# ds2_redraw.net
KiCad netlist of a schematic drawn in EAGLE
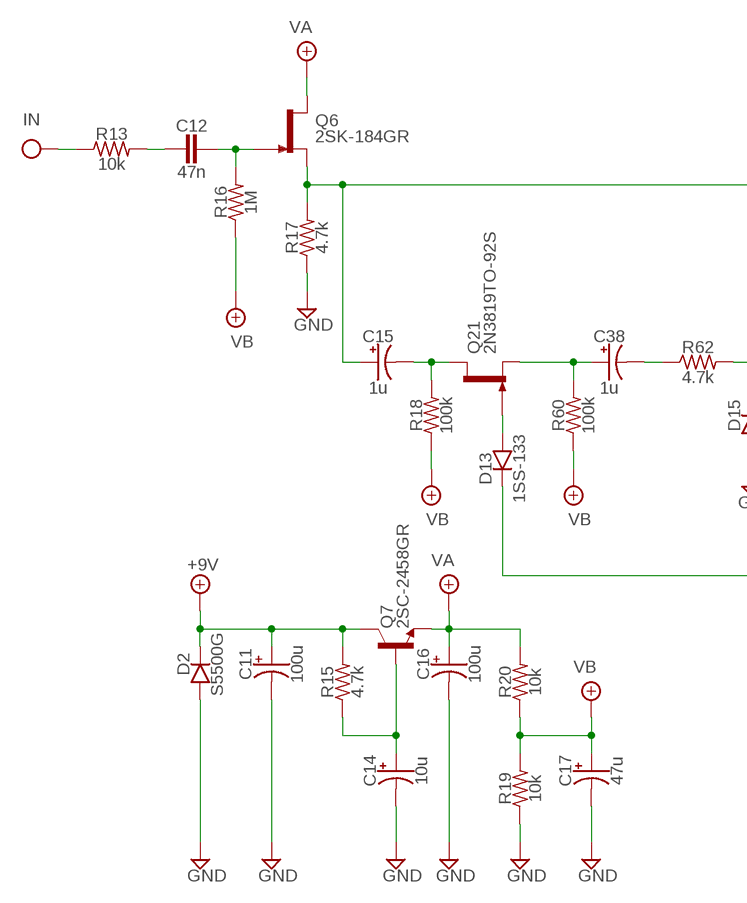
[diagram p0: schematic, sheet 1, part 1 of 2]
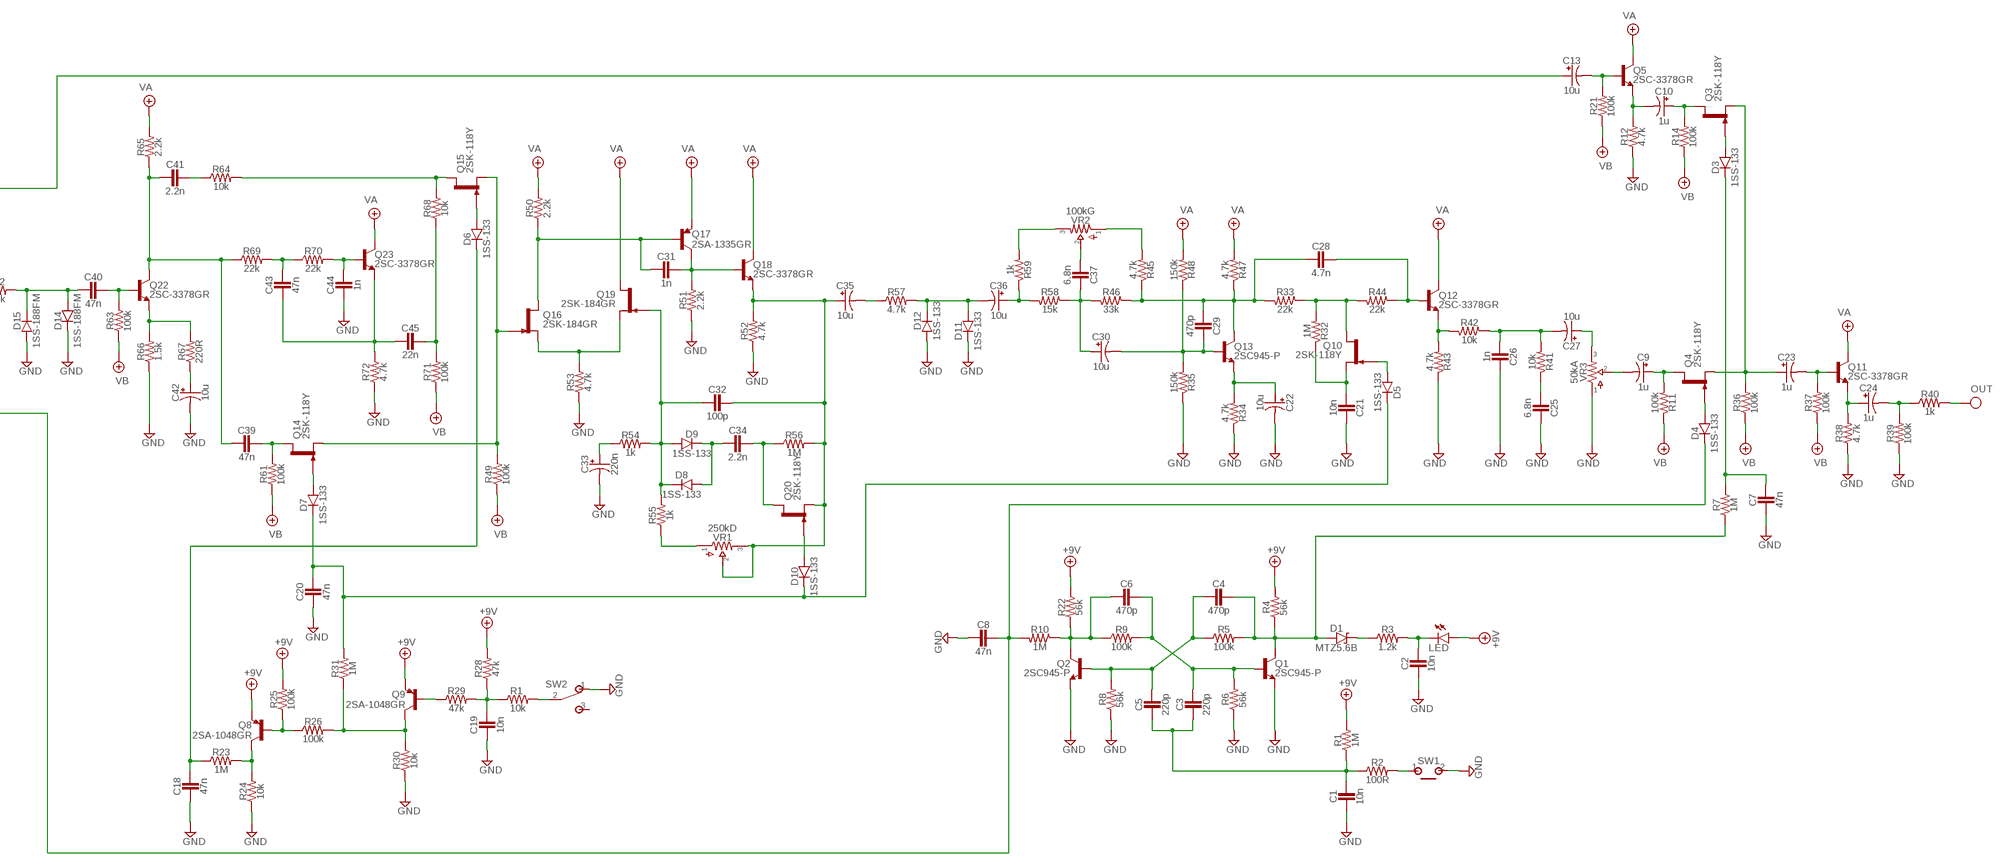
[diagram p1: schematic, sheet 1, part 2 of 2]

(export (version "E")
  (design (tool "Eeschema 10.0.6"))
  (components
    (comp (ref "C1")
      (value "10n")
      (footprint "eagle-import:BOX_SMALL")
      (libsource (lib "eagle-import") (part "CER/FILMBOX.1"))
    )
    (comp (ref "C2")
      (value "10n")
      (footprint "eagle-import:BOX_SMALL")
      (libsource (lib "eagle-import") (part "CER/FILMBOX.1"))
    )
    (comp (ref "C3")
      (value "220p")
      (footprint "eagle-import:BOX_SMALL")
      (libsource (lib "eagle-import") (part "CER/FILMBOX.1"))
    )
    (comp (ref "C4")
      (value "470p")
      (footprint "eagle-import:BOX_SMALL")
      (libsource (lib "eagle-import") (part "CER/FILMBOX.1"))
    )
    (comp (ref "C5")
      (value "220p")
      (footprint "eagle-import:BOX_SMALL")
      (libsource (lib "eagle-import") (part "CER/FILMBOX.1"))
    )
    (comp (ref "C6")
      (value "470p")
      (footprint "eagle-import:BOX_SMALL")
      (libsource (lib "eagle-import") (part "CER/FILMBOX.1"))
    )
    (comp (ref "C7")
      (value "47n")
      (footprint "eagle-import:BOX_SMALL")
      (libsource (lib "eagle-import") (part "CER/FILMBOX.1"))
    )
    (comp (ref "C8")
      (value "47n")
      (footprint "eagle-import:BOX_SMALL")
      (libsource (lib "eagle-import") (part "CER/FILMBOX.1"))
    )
    (comp (ref "C9")
      (value "1u")
      (footprint "eagle-import:040_020")
      (libsource (lib "eagle-import") (part "0400"))
    )
    (comp (ref "C10")
      (value "1u")
      (footprint "eagle-import:040_020")
      (libsource (lib "eagle-import") (part "0400"))
    )
    (comp (ref "C11")
      (value "100u")
      (footprint "eagle-import:040_020")
      (libsource (lib "eagle-import") (part "0400"))
    )
    (comp (ref "C12")
      (value "47n")
      (footprint "eagle-import:BOX_SMALL")
      (libsource (lib "eagle-import") (part "CER/FILMBOX.1"))
    )
    (comp (ref "C13")
      (value "10u")
      (footprint "eagle-import:040_020")
      (libsource (lib "eagle-import") (part "0400"))
    )
    (comp (ref "C14")
      (value "10u")
      (footprint "eagle-import:040_020")
      (libsource (lib "eagle-import") (part "0400"))
    )
    (comp (ref "C15")
      (value "1u")
      (footprint "eagle-import:040_020")
      (libsource (lib "eagle-import") (part "0400"))
    )
    (comp (ref "C16")
      (value "100u")
      (footprint "eagle-import:040_020")
      (libsource (lib "eagle-import") (part "0400"))
    )
    (comp (ref "C17")
      (value "47u")
      (footprint "eagle-import:040_020")
      (libsource (lib "eagle-import") (part "0400"))
    )
    (comp (ref "C18")
      (value "47n")
      (footprint "eagle-import:BOX_SMALL")
      (libsource (lib "eagle-import") (part "CER/FILMBOX.1"))
    )
    (comp (ref "C19")
      (value "10n")
      (footprint "eagle-import:BOX_SMALL")
      (libsource (lib "eagle-import") (part "CER/FILMBOX.1"))
    )
    (comp (ref "C20")
      (value "47n")
      (footprint "eagle-import:BOX_SMALL")
      (libsource (lib "eagle-import") (part "CER/FILMBOX.1"))
    )
    (comp (ref "C21")
      (value "10n")
      (footprint "eagle-import:BOX_SMALL")
      (libsource (lib "eagle-import") (part "CER/FILMBOX.1"))
    )
    (comp (ref "C22")
      (value "10u")
      (footprint "eagle-import:040_020")
      (libsource (lib "eagle-import") (part "0400"))
    )
    (comp (ref "C23")
      (value "1u")
      (footprint "eagle-import:040_020")
      (libsource (lib "eagle-import") (part "0400"))
    )
    (comp (ref "C24")
      (value "1u")
      (footprint "eagle-import:040_020")
      (libsource (lib "eagle-import") (part "0400"))
    )
    (comp (ref "C25")
      (value "6.8n")
      (footprint "eagle-import:BOX_SMALL")
      (libsource (lib "eagle-import") (part "CER/FILMBOX.1"))
    )
    (comp (ref "C26")
      (value "1n")
      (footprint "eagle-import:BOX_SMALL")
      (libsource (lib "eagle-import") (part "CER/FILMBOX.1"))
    )
    (comp (ref "C27")
      (value "10u")
      (footprint "eagle-import:040_020")
      (libsource (lib "eagle-import") (part "0400"))
    )
    (comp (ref "C28")
      (value "4.7n")
      (footprint "eagle-import:BOX_SMALL")
      (libsource (lib "eagle-import") (part "CER/FILMBOX.1"))
    )
    (comp (ref "C29")
      (value "470p")
      (footprint "eagle-import:BOX_SMALL")
      (libsource (lib "eagle-import") (part "CER/FILMBOX.1"))
    )
    (comp (ref "C30")
      (value "10u")
      (footprint "eagle-import:040_020")
      (libsource (lib "eagle-import") (part "0400"))
    )
    (comp (ref "C31")
      (value "1n")
      (footprint "eagle-import:BOX_SMALL")
      (libsource (lib "eagle-import") (part "CER/FILMBOX.1"))
    )
    (comp (ref "C32")
      (value "100p")
      (footprint "eagle-import:BOX_SMALL")
      (libsource (lib "eagle-import") (part "CER/FILMBOX.1"))
    )
    (comp (ref "C33")
      (value "220n")
      (footprint "eagle-import:040_020")
      (libsource (lib "eagle-import") (part "0400"))
    )
    (comp (ref "C34")
      (value "2.2n")
      (footprint "eagle-import:BOX_SMALL")
      (libsource (lib "eagle-import") (part "CER/FILMBOX.1"))
    )
    (comp (ref "C35")
      (value "10u")
      (footprint "eagle-import:040_020")
      (libsource (lib "eagle-import") (part "0400"))
    )
    (comp (ref "C36")
      (value "10u")
      (footprint "eagle-import:040_020")
      (libsource (lib "eagle-import") (part "0400"))
    )
    (comp (ref "C37")
      (value "6.8n")
      (footprint "eagle-import:BOX_SMALL")
      (libsource (lib "eagle-import") (part "CER/FILMBOX.1"))
    )
    (comp (ref "C38")
      (value "1u")
      (footprint "eagle-import:040_020")
      (libsource (lib "eagle-import") (part "0400"))
    )
    (comp (ref "C39")
      (value "47n")
      (footprint "eagle-import:BOX_SMALL")
      (libsource (lib "eagle-import") (part "CER/FILMBOX.1"))
    )
    (comp (ref "C40")
      (value "47n")
      (footprint "eagle-import:BOX_SMALL")
      (libsource (lib "eagle-import") (part "CER/FILMBOX.1"))
    )
    (comp (ref "C41")
      (value "2.2n")
      (footprint "eagle-import:BOX_SMALL")
      (libsource (lib "eagle-import") (part "CER/FILMBOX.1"))
    )
    (comp (ref "C42")
      (value "10u")
      (footprint "eagle-import:040_020")
      (libsource (lib "eagle-import") (part "0400"))
    )
    (comp (ref "C43")
      (value "47n")
      (footprint "eagle-import:BOX_SMALL")
      (libsource (lib "eagle-import") (part "CER/FILMBOX.1"))
    )
    (comp (ref "C44")
      (value "1n")
      (footprint "eagle-import:BOX_SMALL")
      (libsource (lib "eagle-import") (part "CER/FILMBOX.1"))
    )
    (comp (ref "C45")
      (value "22n")
      (footprint "eagle-import:BOX_SMALL")
      (libsource (lib "eagle-import") (part "CER/FILMBOX.1"))
    )
    (comp (ref "D1")
      (value "MTZ5.6B")
      (footprint "eagle-import:DO41-2")
      (libsource (lib "eagle-import") (part "ZENER.2"))
    )
    (comp (ref "D2")
      (value "S5500G")
      (footprint "eagle-import:DO35-2")
      (libsource (lib "eagle-import") (part "DO35.2"))
    )
    (comp (ref "D3")
      (value "1SS-133")
      (footprint "eagle-import:DO35-2")
      (libsource (lib "eagle-import") (part "DO35.2"))
    )
    (comp (ref "D4")
      (value "1SS-133")
      (footprint "eagle-import:DO35-2")
      (libsource (lib "eagle-import") (part "DO35.2"))
    )
    (comp (ref "D5")
      (value "1SS-133")
      (footprint "eagle-import:DO35-2")
      (libsource (lib "eagle-import") (part "DO35.2"))
    )
    (comp (ref "D6")
      (value "1SS-133")
      (footprint "eagle-import:DO35-2")
      (libsource (lib "eagle-import") (part "DO35.2"))
    )
    (comp (ref "D7")
      (value "1SS-133")
      (footprint "eagle-import:DO35-2")
      (libsource (lib "eagle-import") (part "DO35.2"))
    )
    (comp (ref "D8")
      (value "1SS-133")
      (footprint "eagle-import:DO35-2")
      (libsource (lib "eagle-import") (part "DO35.2"))
    )
    (comp (ref "D9")
      (value "1SS-133")
      (footprint "eagle-import:DO35-2")
      (libsource (lib "eagle-import") (part "DO35.2"))
    )
    (comp (ref "D10")
      (value "1SS-133")
      (footprint "eagle-import:DO35-2")
      (libsource (lib "eagle-import") (part "DO35.2"))
    )
    (comp (ref "D11")
      (value "1SS-133")
      (footprint "eagle-import:DO35-2")
      (libsource (lib "eagle-import") (part "DO35.2"))
    )
    (comp (ref "D12")
      (value "1SS-133")
      (footprint "eagle-import:DO35-2")
      (libsource (lib "eagle-import") (part "DO35.2"))
    )
    (comp (ref "D13")
      (value "1SS-133")
      (footprint "eagle-import:DO35-2")
      (libsource (lib "eagle-import") (part "DO35.2"))
    )
    (comp (ref "D14")
      (value "1SS-188FM")
      (footprint "eagle-import:DO35-2")
      (libsource (lib "eagle-import") (part "DO35.2"))
    )
    (comp (ref "D15")
      (value "1SS-188FM")
      (footprint "eagle-import:DO35-2")
      (libsource (lib "eagle-import") (part "DO35.2"))
    )
    (comp (ref "LED")
      (value "LED")
      (footprint "eagle-import:3MM_D")
      (libsource (lib "eagle-import") (part "LED"))
    )
    (comp (ref "Q1")
      (value "2SC945-P")
      (footprint "eagle-import:TO92-")
      (libsource (lib "eagle-import") (part "2SC828A"))
    )
    (comp (ref "Q2")
      (value "2SC945-P")
      (footprint "eagle-import:TO92-")
      (libsource (lib "eagle-import") (part "2SC828A"))
    )
    (comp (ref "Q3")
      (value "2SK-118Y")
      (footprint "eagle-import:TO92-")
      (libsource (lib "eagle-import") (part "2N3819TO-92S"))
    )
    (comp (ref "Q4")
      (value "2SK-118Y")
      (footprint "eagle-import:TO92-")
      (libsource (lib "eagle-import") (part "2N3819TO-92S"))
    )
    (comp (ref "Q5")
      (value "2SC-3378GR")
      (footprint "eagle-import:TO92-")
      (libsource (lib "eagle-import") (part "2SC828A"))
    )
    (comp (ref "Q6")
      (value "2SK-184GR")
      (footprint "eagle-import:TO92-")
      (libsource (lib "eagle-import") (part "2N3819TO-92S"))
    )
    (comp (ref "Q7")
      (value "2SC-2458GR")
      (footprint "eagle-import:TO92-")
      (libsource (lib "eagle-import") (part "2SC828A"))
    )
    (comp (ref "Q8")
      (value "2SA-1048GR")
      (footprint "eagle-import:TO92-")
      (libsource (lib "eagle-import") (part "2N3906-"))
    )
    (comp (ref "Q9")
      (value "2SA-1048GR")
      (footprint "eagle-import:TO92-")
      (libsource (lib "eagle-import") (part "2N3906-"))
    )
    (comp (ref "Q10")
      (value "2SK-118Y")
      (footprint "eagle-import:TO92-")
      (libsource (lib "eagle-import") (part "2N3819TO-92S"))
    )
    (comp (ref "Q11")
      (value "2SC-3378GR")
      (footprint "eagle-import:TO92-")
      (libsource (lib "eagle-import") (part "2SC828A"))
    )
    (comp (ref "Q12")
      (value "2SC-3378GR")
      (footprint "eagle-import:TO92-")
      (libsource (lib "eagle-import") (part "2SC828A"))
    )
    (comp (ref "Q13")
      (value "2SC945-P")
      (footprint "eagle-import:TO92-")
      (libsource (lib "eagle-import") (part "2SC828A"))
    )
    (comp (ref "Q14")
      (value "2SK-118Y")
      (footprint "eagle-import:TO92-")
      (libsource (lib "eagle-import") (part "2N3819TO-92S"))
    )
    (comp (ref "Q15")
      (value "2SK-118Y")
      (footprint "eagle-import:TO92-")
      (libsource (lib "eagle-import") (part "2N3819TO-92S"))
    )
    (comp (ref "Q16")
      (value "2SK-184GR")
      (footprint "eagle-import:TO92-")
      (libsource (lib "eagle-import") (part "2N3819TO-92S"))
    )
    (comp (ref "Q17")
      (value "2SA-1335GR")
      (footprint "eagle-import:TO92-")
      (libsource (lib "eagle-import") (part "2N3906-"))
    )
    (comp (ref "Q18")
      (value "2SC-3378GR")
      (footprint "eagle-import:TO92-")
      (libsource (lib "eagle-import") (part "2SC828A"))
    )
    (comp (ref "Q19")
      (value "2SK-184GR")
      (footprint "eagle-import:TO92-")
      (libsource (lib "eagle-import") (part "2N3819TO-92S"))
    )
    (comp (ref "Q20")
      (value "2SK-118Y")
      (footprint "eagle-import:TO92-")
      (libsource (lib "eagle-import") (part "2N3819TO-92S"))
    )
    (comp (ref "Q21")
      (value "2N3819TO-92S")
      (footprint "eagle-import:TO92-")
      (libsource (lib "eagle-import") (part "2N3819TO-92S"))
    )
    (comp (ref "Q22")
      (value "2SC-3378GR")
      (footprint "eagle-import:TO92-")
      (libsource (lib "eagle-import") (part "2SC828A"))
    )
    (comp (ref "Q23")
      (value "2SC-3378GR")
      (footprint "eagle-import:TO92-")
      (libsource (lib "eagle-import") (part "2SC828A"))
    )
    (comp (ref "R1")
      (value "1M")
      (footprint "eagle-import:R0207_3")
      (libsource (lib "eagle-import") (part "R_.3B"))
    )
    (comp (ref "R1 ")
      (value "10k")
      (footprint "eagle-import:R0207_3")
      (libsource (lib "eagle-import") (part "R_.3B"))
    )
    (comp (ref "R2")
      (value "100R")
      (footprint "eagle-import:R0207_3")
      (libsource (lib "eagle-import") (part "R_.3B"))
    )
    (comp (ref "R3")
      (value "1.2k")
      (footprint "eagle-import:R0207_3")
      (libsource (lib "eagle-import") (part "R_.3B"))
    )
    (comp (ref "R4")
      (value "56k")
      (footprint "eagle-import:R0207_3")
      (libsource (lib "eagle-import") (part "R_.3B"))
    )
    (comp (ref "R5")
      (value "100k")
      (footprint "eagle-import:R0207_3")
      (libsource (lib "eagle-import") (part "R_.3B"))
    )
    (comp (ref "R6")
      (value "56k")
      (footprint "eagle-import:R0207_3")
      (libsource (lib "eagle-import") (part "R_.3B"))
    )
    (comp (ref "R7")
      (value "1M")
      (footprint "eagle-import:R0207_3")
      (libsource (lib "eagle-import") (part "R_.3B"))
    )
    (comp (ref "R8")
      (value "56k")
      (footprint "eagle-import:R0207_3")
      (libsource (lib "eagle-import") (part "R_.3B"))
    )
    (comp (ref "R9")
      (value "100k")
      (footprint "eagle-import:R0207_3")
      (libsource (lib "eagle-import") (part "R_.3B"))
    )
    (comp (ref "R10")
      (value "1M")
      (footprint "eagle-import:R0207_3")
      (libsource (lib "eagle-import") (part "R_.3B"))
    )
    (comp (ref "R11")
      (value "100k")
      (footprint "eagle-import:R0207_3")
      (libsource (lib "eagle-import") (part "R_.3B"))
    )
    (comp (ref "R12")
      (value "4.7k")
      (footprint "eagle-import:R0207_3")
      (libsource (lib "eagle-import") (part "R_.3B"))
    )
    (comp (ref "R13")
      (value "10k")
      (footprint "eagle-import:R0207_3")
      (libsource (lib "eagle-import") (part "R_.3B"))
    )
    (comp (ref "R14")
      (value "100k")
      (footprint "eagle-import:R0207_3")
      (libsource (lib "eagle-import") (part "R_.3B"))
    )
    (comp (ref "R15")
      (value "4.7k")
      (footprint "eagle-import:R0207_3")
      (libsource (lib "eagle-import") (part "R_.3B"))
    )
    (comp (ref "R16")
      (value "1M")
      (footprint "eagle-import:R0207_3")
      (libsource (lib "eagle-import") (part "R_.3B"))
    )
    (comp (ref "R17")
      (value "4.7k")
      (footprint "eagle-import:R0207_3")
      (libsource (lib "eagle-import") (part "R_.3B"))
    )
    (comp (ref "R18")
      (value "100k")
      (footprint "eagle-import:R0207_3")
      (libsource (lib "eagle-import") (part "R_.3B"))
    )
    (comp (ref "R19")
      (value "10k")
      (footprint "eagle-import:R0207_3")
      (libsource (lib "eagle-import") (part "R_.3B"))
    )
    (comp (ref "R20")
      (value "10k")
      (footprint "eagle-import:R0207_3")
      (libsource (lib "eagle-import") (part "R_.3B"))
    )
    (comp (ref "R21")
      (value "100k")
      (footprint "eagle-import:R0207_3")
      (libsource (lib "eagle-import") (part "R_.3B"))
    )
    (comp (ref "R22")
      (value "56k")
      (footprint "eagle-import:R0207_3")
      (libsource (lib "eagle-import") (part "R_.3B"))
    )
    (comp (ref "R23")
      (value "1M")
      (footprint "eagle-import:R0207_3")
      (libsource (lib "eagle-import") (part "R_.3B"))
    )
    (comp (ref "R24")
      (value "10k")
      (footprint "eagle-import:R0207_3")
      (libsource (lib "eagle-import") (part "R_.3B"))
    )
    (comp (ref "R25")
      (value "100k")
      (footprint "eagle-import:R0207_3")
      (libsource (lib "eagle-import") (part "R_.3B"))
    )
    (comp (ref "R26")
      (value "100k")
      (footprint "eagle-import:R0207_3")
      (libsource (lib "eagle-import") (part "R_.3B"))
    )
    (comp (ref "R28")
      (value "47k")
      (footprint "eagle-import:R0207_3")
      (libsource (lib "eagle-import") (part "R_.3B"))
    )
    (comp (ref "R29")
      (value "47k")
      (footprint "eagle-import:R0207_3")
      (libsource (lib "eagle-import") (part "R_.3B"))
    )
    (comp (ref "R30")
      (value "10k")
      (footprint "eagle-import:R0207_3")
      (libsource (lib "eagle-import") (part "R_.3B"))
    )
    (comp (ref "R31")
      (value "1M")
      (footprint "eagle-import:R0207_3")
      (libsource (lib "eagle-import") (part "R_.3B"))
    )
    (comp (ref "R32")
      (value "1M")
      (footprint "eagle-import:R0207_3")
      (libsource (lib "eagle-import") (part "R_.3B"))
    )
    (comp (ref "R33")
      (value "22k")
      (footprint "eagle-import:R0207_3")
      (libsource (lib "eagle-import") (part "R_.3B"))
    )
    (comp (ref "R34")
      (value "4.7k")
      (footprint "eagle-import:R0207_3")
      (libsource (lib "eagle-import") (part "R_.3B"))
    )
    (comp (ref "R35")
      (value "150k")
      (footprint "eagle-import:R0207_3")
      (libsource (lib "eagle-import") (part "R_.3B"))
    )
    (comp (ref "R36")
      (value "100k")
      (footprint "eagle-import:R0207_3")
      (libsource (lib "eagle-import") (part "R_.3B"))
    )
    (comp (ref "R37")
      (value "100k")
      (footprint "eagle-import:R0207_3")
      (libsource (lib "eagle-import") (part "R_.3B"))
    )
    (comp (ref "R38")
      (value "4.7k")
      (footprint "eagle-import:R0207_3")
      (libsource (lib "eagle-import") (part "R_.3B"))
    )
    (comp (ref "R39")
      (value "100k")
      (footprint "eagle-import:R0207_3")
      (libsource (lib "eagle-import") (part "R_.3B"))
    )
    (comp (ref "R40")
      (value "1k")
      (footprint "eagle-import:R0207_3")
      (libsource (lib "eagle-import") (part "R_.3B"))
    )
    (comp (ref "R41")
      (value "10k")
      (footprint "eagle-import:R0207_3")
      (libsource (lib "eagle-import") (part "R_.3B"))
    )
    (comp (ref "R42")
      (value "10k")
      (footprint "eagle-import:R0207_3")
      (libsource (lib "eagle-import") (part "R_.3B"))
    )
    (comp (ref "R43")
      (value "4.7k")
      (footprint "eagle-import:R0207_3")
      (libsource (lib "eagle-import") (part "R_.3B"))
    )
    (comp (ref "R44")
      (value "22k")
      (footprint "eagle-import:R0207_3")
      (libsource (lib "eagle-import") (part "R_.3B"))
    )
    (comp (ref "R45")
      (value "4.7k")
      (footprint "eagle-import:R0207_3")
      (libsource (lib "eagle-import") (part "R_.3B"))
    )
    (comp (ref "R46")
      (value "33k")
      (footprint "eagle-import:R0207_3")
      (libsource (lib "eagle-import") (part "R_.3B"))
    )
    (comp (ref "R47")
      (value "4.7k")
      (footprint "eagle-import:R0207_3")
      (libsource (lib "eagle-import") (part "R_.3B"))
    )
    (comp (ref "R48")
      (value "150k")
      (footprint "eagle-import:R0207_3")
      (libsource (lib "eagle-import") (part "R_.3B"))
    )
    (comp (ref "R49")
      (value "100k")
      (footprint "eagle-import:R0207_3")
      (libsource (lib "eagle-import") (part "R_.3B"))
    )
    (comp (ref "R50")
      (value "2.2k")
      (footprint "eagle-import:R0207_3")
      (libsource (lib "eagle-import") (part "R_.3B"))
    )
    (comp (ref "R51")
      (value "2.2k")
      (footprint "eagle-import:R0207_3")
      (libsource (lib "eagle-import") (part "R_.3B"))
    )
    (comp (ref "R52")
      (value "4.7k")
      (footprint "eagle-import:R0207_3")
      (libsource (lib "eagle-import") (part "R_.3B"))
    )
    (comp (ref "R53")
      (value "4.7k")
      (footprint "eagle-import:R0207_3")
      (libsource (lib "eagle-import") (part "R_.3B"))
    )
    (comp (ref "R54")
      (value "1k")
      (footprint "eagle-import:R0207_3")
      (libsource (lib "eagle-import") (part "R_.3B"))
    )
    (comp (ref "R55")
      (value "1k")
      (footprint "eagle-import:R0207_3")
      (libsource (lib "eagle-import") (part "R_.3B"))
    )
    (comp (ref "R56")
      (value "1M")
      (footprint "eagle-import:R0207_3")
      (libsource (lib "eagle-import") (part "R_.3B"))
    )
    (comp (ref "R57")
      (value "4.7k")
      (footprint "eagle-import:R0207_3")
      (libsource (lib "eagle-import") (part "R_.3B"))
    )
    (comp (ref "R58")
      (value "15k")
      (footprint "eagle-import:R0207_3")
      (libsource (lib "eagle-import") (part "R_.3B"))
    )
    (comp (ref "R59")
      (value "1k")
      (footprint "eagle-import:R0207_3")
      (libsource (lib "eagle-import") (part "R_.3B"))
    )
    (comp (ref "R60")
      (value "100k")
      (footprint "eagle-import:R0207_3")
      (libsource (lib "eagle-import") (part "R_.3B"))
    )
    (comp (ref "R61")
      (value "100k")
      (footprint "eagle-import:R0207_3")
      (libsource (lib "eagle-import") (part "R_.3B"))
    )
    (comp (ref "R62")
      (value "4.7k")
      (footprint "eagle-import:R0207_3")
      (libsource (lib "eagle-import") (part "R_.3B"))
    )
    (comp (ref "R63")
      (value "100k")
      (footprint "eagle-import:R0207_3")
      (libsource (lib "eagle-import") (part "R_.3B"))
    )
    (comp (ref "R64")
      (value "10k")
      (footprint "eagle-import:R0207_3")
      (libsource (lib "eagle-import") (part "R_.3B"))
    )
    (comp (ref "R65")
      (value "2.2k")
      (footprint "eagle-import:R0207_3")
      (libsource (lib "eagle-import") (part "R_.3B"))
    )
    (comp (ref "R66")
      (value "1.5k")
      (footprint "eagle-import:R0207_3")
      (libsource (lib "eagle-import") (part "R_.3B"))
    )
    (comp (ref "R67")
      (value "220R")
      (footprint "eagle-import:R0207_3")
      (libsource (lib "eagle-import") (part "R_.3B"))
    )
    (comp (ref "R68")
      (value "10k")
      (footprint "eagle-import:R0207_3")
      (libsource (lib "eagle-import") (part "R_.3B"))
    )
    (comp (ref "R69")
      (value "22k")
      (footprint "eagle-import:R0207_3")
      (libsource (lib "eagle-import") (part "R_.3B"))
    )
    (comp (ref "R70")
      (value "22k")
      (footprint "eagle-import:R0207_3")
      (libsource (lib "eagle-import") (part "R_.3B"))
    )
    (comp (ref "R71")
      (value "100k")
      (footprint "eagle-import:R0207_3")
      (libsource (lib "eagle-import") (part "R_.3B"))
    )
    (comp (ref "R72")
      (value "4.7k")
      (footprint "eagle-import:R0207_3")
      (libsource (lib "eagle-import") (part "R_.3B"))
    )
    (comp (ref "SW1")
      (value "MOMENTARY")
      (footprint "eagle-import:SPST")
      (libsource (lib "eagle-import") (part "MOMENTARY"))
    )
    (comp (ref "SW2")
      (value "SPDT")
      (footprint "eagle-import:M9040P")
      (libsource (lib "eagle-import") (part "SPDT"))
    )
    (comp (ref "VR1")
      (value "250kD")
      (footprint "eagle-import:16MM")
      (libsource (lib "eagle-import") (part "POTS16MM"))
    )
    (comp (ref "VR2")
      (value "100kG")
      (footprint "eagle-import:16MM")
      (libsource (lib "eagle-import") (part "POTS16MM"))
    )
    (comp (ref "VR3")
      (value "50kA")
      (footprint "eagle-import:16MM")
      (libsource (lib "eagle-import") (part "POTS16MM"))
    )
  )
  (nets
    (net (code "1") (name "+9V") (class "Default")
      (node (ref "C11") (pin "+") (pinfunction "+_+") (pintype "passive"))
      (node (ref "D2") (pin "C") (pinfunction "C_C") (pintype "passive"))
      (node (ref "LED") (pin "ANODE") (pinfunction "A_ANODE") (pintype "passive"))
      (node (ref "Q7") (pin "2") (pinfunction "C_2") (pintype "passive"))
      (node (ref "Q8") (pin "3") (pinfunction "E_3") (pintype "passive"))
      (node (ref "Q9") (pin "3") (pinfunction "E_3") (pintype "passive"))
      (node (ref "R1") (pin "2") (pinfunction "2_2") (pintype "passive"))
      (node (ref "R15") (pin "2") (pinfunction "2_2") (pintype "passive"))
      (node (ref "R22") (pin "2") (pinfunction "2_2") (pintype "passive"))
      (node (ref "R25") (pin "2") (pinfunction "2_2") (pintype "passive"))
      (node (ref "R28") (pin "2") (pinfunction "2_2") (pintype "passive"))
      (node (ref "R4") (pin "2") (pinfunction "2_2") (pintype "passive"))
    )
    (net (code "2") (name "GND") (class "Default")
      (node (ref "C1") (pin "2") (pinfunction "2_2") (pintype "passive"))
      (node (ref "C11") (pin "-") (pinfunction "-_-") (pintype "passive"))
      (node (ref "C14") (pin "-") (pinfunction "-_-") (pintype "passive"))
      (node (ref "C16") (pin "-") (pinfunction "-_-") (pintype "passive"))
      (node (ref "C17") (pin "-") (pinfunction "-_-") (pintype "passive"))
      (node (ref "C18") (pin "2") (pinfunction "2_2") (pintype "passive"))
      (node (ref "C19") (pin "2") (pinfunction "2_2") (pintype "passive"))
      (node (ref "C2") (pin "2") (pinfunction "2_2") (pintype "passive"))
      (node (ref "C20") (pin "2") (pinfunction "2_2") (pintype "passive"))
      (node (ref "C21") (pin "2") (pinfunction "2_2") (pintype "passive"))
      (node (ref "C22") (pin "-") (pinfunction "-_-") (pintype "passive"))
      (node (ref "C25") (pin "2") (pinfunction "2_2") (pintype "passive"))
      (node (ref "C26") (pin "2") (pinfunction "2_2") (pintype "passive"))
      (node (ref "C33") (pin "-") (pinfunction "-_-") (pintype "passive"))
      (node (ref "C42") (pin "-") (pinfunction "-_-") (pintype "passive"))
      (node (ref "C44") (pin "2") (pinfunction "2_2") (pintype "passive"))
      (node (ref "C7") (pin "2") (pinfunction "2_2") (pintype "passive"))
      (node (ref "C8") (pin "2") (pinfunction "2_2") (pintype "passive"))
      (node (ref "D11") (pin "C") (pinfunction "C_C") (pintype "passive"))
      (node (ref "D12") (pin "A") (pinfunction "A_A") (pintype "passive"))
      (node (ref "D14") (pin "C") (pinfunction "C_C") (pintype "passive"))
      (node (ref "D15") (pin "A") (pinfunction "A_A") (pintype "passive"))
      (node (ref "D2") (pin "A") (pinfunction "A_A") (pintype "passive"))
      (node (ref "Q1") (pin "3") (pinfunction "E_3") (pintype "passive"))
      (node (ref "Q2") (pin "3") (pinfunction "E_3") (pintype "passive"))
      (node (ref "R12") (pin "1") (pinfunction "1_1") (pintype "passive"))
      (node (ref "R17") (pin "1") (pinfunction "1_1") (pintype "passive"))
      (node (ref "R19") (pin "1") (pinfunction "1_1") (pintype "passive"))
      (node (ref "R24") (pin "1") (pinfunction "1_1") (pintype "passive"))
      (node (ref "R30") (pin "1") (pinfunction "1_1") (pintype "passive"))
      (node (ref "R34") (pin "1") (pinfunction "1_1") (pintype "passive"))
      (node (ref "R35") (pin "1") (pinfunction "1_1") (pintype "passive"))
      (node (ref "R38") (pin "1") (pinfunction "1_1") (pintype "passive"))
      (node (ref "R39") (pin "1") (pinfunction "1_1") (pintype "passive"))
      (node (ref "R43") (pin "1") (pinfunction "1_1") (pintype "passive"))
      (node (ref "R51") (pin "1") (pinfunction "1_1") (pintype "passive"))
      (node (ref "R52") (pin "1") (pinfunction "1_1") (pintype "passive"))
      (node (ref "R53") (pin "1") (pinfunction "1_1") (pintype "passive"))
      (node (ref "R6") (pin "1") (pinfunction "1_1") (pintype "passive"))
      (node (ref "R66") (pin "1") (pinfunction "1_1") (pintype "passive"))
      (node (ref "R72") (pin "1") (pinfunction "1_1") (pintype "passive"))
      (node (ref "R8") (pin "1") (pinfunction "1_1") (pintype "passive"))
      (node (ref "SW1") (pin "2") (pinfunction "S_2") (pintype "passive"))
      (node (ref "SW2") (pin "1") (pinfunction "O_1") (pintype "passive"))
      (node (ref "VR3") (pin "1") (pinfunction "1_1") (pintype "passive"))
    )
    (net (code "3") (name "IN") (class "Default")
      (node (ref "R13") (pin "1") (pinfunction "1_1") (pintype "passive"))
    )
    (net (code "4") (name "Net-(C1-Pad1)") (class "Default")
      (node (ref "C1") (pin "1") (pinfunction "1_1") (pintype "passive"))
      (node (ref "C3") (pin "2") (pinfunction "2_2") (pintype "passive"))
      (node (ref "C5") (pin "2") (pinfunction "2_2") (pintype "passive"))
      (node (ref "R1") (pin "1") (pinfunction "1_1") (pintype "passive"))
      (node (ref "R2") (pin "1") (pinfunction "1_1") (pintype "passive"))
    )
    (net (code "5") (name "Net-(C7-Pad1)") (class "Default")
      (node (ref "C7") (pin "1") (pinfunction "1_1") (pintype "passive"))
      (node (ref "D3") (pin "C") (pinfunction "C_C") (pintype "passive"))
      (node (ref "R7") (pin "2") (pinfunction "2_2") (pintype "passive"))
    )
    (net (code "6") (name "Net-(C8-Pad1)") (class "Default")
      (node (ref "C8") (pin "1") (pinfunction "1_1") (pintype "passive"))
      (node (ref "D13") (pin "C") (pinfunction "C_C") (pintype "passive"))
      (node (ref "D4") (pin "C") (pinfunction "C_C") (pintype "passive"))
      (node (ref "R10") (pin "2") (pinfunction "2_2") (pintype "passive"))
    )
    (net (code "7") (name "Net-(C9-Pad-)") (class "Default")
      (node (ref "C9") (pin "-") (pinfunction "-_-") (pintype "passive"))
      (node (ref "VR3") (pin "2") (pinfunction "2_2") (pintype "passive"))
    )
    (net (code "8") (name "Net-(C12-Pad2)") (class "Default")
      (node (ref "C12") (pin "2") (pinfunction "2_2") (pintype "passive"))
      (node (ref "R13") (pin "2") (pinfunction "2_2") (pintype "passive"))
    )
    (net (code "9") (name "Net-(C18-Pad1)") (class "Default")
      (node (ref "C18") (pin "1") (pinfunction "1_1") (pintype "passive"))
      (node (ref "D6") (pin "C") (pinfunction "C_C") (pintype "passive"))
      (node (ref "R23") (pin "1") (pinfunction "1_1") (pintype "passive"))
    )
    (net (code "10") (name "Net-(C19-Pad1)") (class "Default")
      (node (ref "C19") (pin "1") (pinfunction "1_1") (pintype "passive"))
      (node (ref "R1 ") (pin "1") (pinfunction "1_1") (pintype "passive"))
      (node (ref "R28") (pin "1") (pinfunction "1_1") (pintype "passive"))
      (node (ref "R29") (pin "2") (pinfunction "2_2") (pintype "passive"))
    )
    (net (code "11") (name "Net-(C20-Pad1)") (class "Default")
      (node (ref "C20") (pin "1") (pinfunction "1_1") (pintype "passive"))
      (node (ref "D10") (pin "C") (pinfunction "C_C") (pintype "passive"))
      (node (ref "D5") (pin "C") (pinfunction "C_C") (pintype "passive"))
      (node (ref "D7") (pin "C") (pinfunction "C_C") (pintype "passive"))
      (node (ref "R31") (pin "2") (pinfunction "2_2") (pintype "passive"))
    )
    (net (code "12") (name "Net-(C24-Pad-)") (class "Default")
      (node (ref "C24") (pin "-") (pinfunction "-_-") (pintype "passive"))
      (node (ref "R39") (pin "2") (pinfunction "2_2") (pintype "passive"))
      (node (ref "R40") (pin "1") (pinfunction "1_1") (pintype "passive"))
    )
    (net (code "13") (name "Net-(C25-Pad1)") (class "Default")
      (node (ref "C25") (pin "1") (pinfunction "1_1") (pintype "passive"))
      (node (ref "R41") (pin "1") (pinfunction "1_1") (pintype "passive"))
    )
    (net (code "14") (name "Net-(C26-Pad1)") (class "Default")
      (node (ref "C26") (pin "1") (pinfunction "1_1") (pintype "passive"))
      (node (ref "C27") (pin "-") (pinfunction "-_-") (pintype "passive"))
      (node (ref "R41") (pin "2") (pinfunction "2_2") (pintype "passive"))
      (node (ref "R42") (pin "1") (pinfunction "1_1") (pintype "passive"))
    )
    (net (code "15") (name "Net-(C27-Pad+)") (class "Default")
      (node (ref "C27") (pin "+") (pinfunction "+_+") (pintype "passive"))
      (node (ref "VR3") (pin "3") (pinfunction "3_3") (pintype "passive"))
    )
    (net (code "16") (name "Net-(C30-Pad+)") (class "Default")
      (node (ref "C30") (pin "+") (pinfunction "+_+") (pintype "passive"))
      (node (ref "C37") (pin "2") (pinfunction "2_2") (pintype "passive"))
      (node (ref "R46") (pin "2") (pinfunction "2_2") (pintype "passive"))
      (node (ref "R58") (pin "1") (pinfunction "1_1") (pintype "passive"))
    )
    (net (code "17") (name "Net-(C33-Pad+)") (class "Default")
      (node (ref "C33") (pin "+") (pinfunction "+_+") (pintype "passive"))
      (node (ref "R54") (pin "1") (pinfunction "1_1") (pintype "passive"))
    )
    (net (code "18") (name "Net-(C34-Pad2)") (class "Default")
      (node (ref "C34") (pin "2") (pinfunction "2_2") (pintype "passive"))
      (node (ref "D8") (pin "A") (pinfunction "A_A") (pintype "passive"))
      (node (ref "D9") (pin "C") (pinfunction "C_C") (pintype "passive"))
    )
    (net (code "19") (name "Net-(C35-Pad-)") (class "Default")
      (node (ref "C35") (pin "-") (pinfunction "-_-") (pintype "passive"))
      (node (ref "R57") (pin "1") (pinfunction "1_1") (pintype "passive"))
    )
    (net (code "20") (name "Net-(C36-Pad+)") (class "Default")
      (node (ref "C36") (pin "+") (pinfunction "+_+") (pintype "passive"))
      (node (ref "R58") (pin "2") (pinfunction "2_2") (pintype "passive"))
      (node (ref "R59") (pin "1") (pinfunction "1_1") (pintype "passive"))
    )
    (net (code "21") (name "Net-(C36-Pad-)") (class "Default")
      (node (ref "C36") (pin "-") (pinfunction "-_-") (pintype "passive"))
      (node (ref "D11") (pin "A") (pinfunction "A_A") (pintype "passive"))
      (node (ref "D12") (pin "C") (pinfunction "C_C") (pintype "passive"))
      (node (ref "R57") (pin "2") (pinfunction "2_2") (pintype "passive"))
    )
    (net (code "22") (name "Net-(C37-Pad1)") (class "Default")
      (node (ref "C37") (pin "1") (pinfunction "1_1") (pintype "passive"))
      (node (ref "VR2") (pin "2") (pinfunction "2_2") (pintype "passive"))
    )
    (net (code "23") (name "Net-(C38-Pad-)") (class "Default")
      (node (ref "C38") (pin "-") (pinfunction "-_-") (pintype "passive"))
      (node (ref "R62") (pin "1") (pinfunction "1_1") (pintype "passive"))
    )
    (net (code "24") (name "Net-(C40-Pad2)") (class "Default")
      (node (ref "C40") (pin "2") (pinfunction "2_2") (pintype "passive"))
      (node (ref "D14") (pin "A") (pinfunction "A_A") (pintype "passive"))
      (node (ref "D15") (pin "C") (pinfunction "C_C") (pintype "passive"))
      (node (ref "R62") (pin "2") (pinfunction "2_2") (pintype "passive"))
    )
    (net (code "25") (name "Net-(C41-Pad1)") (class "Default")
      (node (ref "C41") (pin "1") (pinfunction "1_1") (pintype "passive"))
      (node (ref "R64") (pin "1") (pinfunction "1_1") (pintype "passive"))
    )
    (net (code "26") (name "Net-(C42-Pad+)") (class "Default")
      (node (ref "C42") (pin "+") (pinfunction "+_+") (pintype "passive"))
      (node (ref "R67") (pin "1") (pinfunction "1_1") (pintype "passive"))
    )
    (net (code "27") (name "Net-(C43-Pad1)") (class "Default")
      (node (ref "C43") (pin "1") (pinfunction "1_1") (pintype "passive"))
      (node (ref "R69") (pin "2") (pinfunction "2_2") (pintype "passive"))
      (node (ref "R70") (pin "1") (pinfunction "1_1") (pintype "passive"))
    )
    (net (code "28") (name "Net-(C45-Pad1)") (class "Default")
      (node (ref "C45") (pin "1") (pinfunction "1_1") (pintype "passive"))
      (node (ref "R68") (pin "1") (pinfunction "1_1") (pintype "passive"))
      (node (ref "R71") (pin "2") (pinfunction "2_2") (pintype "passive"))
    )
    (net (code "29") (name "Net-(D1-PadC)") (class "Default")
      (node (ref "D1") (pin "C") (pinfunction "C_C") (pintype "passive"))
      (node (ref "R3") (pin "1") (pinfunction "1_1") (pintype "passive"))
    )
    (net (code "30") (name "Net-(LED-C)") (class "Default")
      (node (ref "C2") (pin "1") (pinfunction "1_1") (pintype "passive"))
      (node (ref "LED") (pin "P$1") (pinfunction "C_P$1") (pintype "passive"))
      (node (ref "R3") (pin "2") (pinfunction "2_2") (pintype "passive"))
    )
    (net (code "31") (name "Net-(Q1-B)") (class "Default")
      (node (ref "C3") (pin "1") (pinfunction "1_1") (pintype "passive"))
      (node (ref "C6") (pin "1") (pinfunction "1_1") (pintype "passive"))
      (node (ref "Q1") (pin "1") (pinfunction "B_1") (pintype "passive"))
      (node (ref "R6") (pin "2") (pinfunction "2_2") (pintype "passive"))
      (node (ref "R9") (pin "2") (pinfunction "2_2") (pintype "passive"))
    )
    (net (code "32") (name "Net-(Q1-C)") (class "Default")
      (node (ref "C4") (pin "1") (pinfunction "1_1") (pintype "passive"))
      (node (ref "D1") (pin "A") (pinfunction "A_A") (pintype "passive"))
      (node (ref "Q1") (pin "2") (pinfunction "C_2") (pintype "passive"))
      (node (ref "R4") (pin "1") (pinfunction "1_1") (pintype "passive"))
      (node (ref "R5") (pin "2") (pinfunction "2_2") (pintype "passive"))
      (node (ref "R7") (pin "1") (pinfunction "1_1") (pintype "passive"))
    )
    (net (code "33") (name "Net-(Q2-B)") (class "Default")
      (node (ref "C4") (pin "2") (pinfunction "2_2") (pintype "passive"))
      (node (ref "C5") (pin "1") (pinfunction "1_1") (pintype "passive"))
      (node (ref "Q2") (pin "1") (pinfunction "B_1") (pintype "passive"))
      (node (ref "R5") (pin "1") (pinfunction "1_1") (pintype "passive"))
      (node (ref "R8") (pin "2") (pinfunction "2_2") (pintype "passive"))
    )
    (net (code "34") (name "Net-(Q2-C)") (class "Default")
      (node (ref "C6") (pin "2") (pinfunction "2_2") (pintype "passive"))
      (node (ref "Q2") (pin "2") (pinfunction "C_2") (pintype "passive"))
      (node (ref "R10") (pin "1") (pinfunction "1_1") (pintype "passive"))
      (node (ref "R22") (pin "1") (pinfunction "1_1") (pintype "passive"))
      (node (ref "R9") (pin "1") (pinfunction "1_1") (pintype "passive"))
    )
    (net (code "35") (name "Net-(Q3-D)") (class "Default")
      (node (ref "C10") (pin "+") (pinfunction "+_+") (pintype "passive"))
      (node (ref "Q3") (pin "3") (pinfunction "D_3") (pintype "passive"))
      (node (ref "R14") (pin "2") (pinfunction "2_2") (pintype "passive"))
    )
    (net (code "36") (name "Net-(Q3-G)") (class "Default")
      (node (ref "D3") (pin "A") (pinfunction "A_A") (pintype "passive"))
      (node (ref "Q3") (pin "2") (pinfunction "G_2") (pintype "passive"))
    )
    (net (code "37") (name "Net-(Q3-S)") (class "Default")
      (node (ref "C23") (pin "+") (pinfunction "+_+") (pintype "passive"))
      (node (ref "Q3") (pin "1") (pinfunction "S_1") (pintype "passive"))
      (node (ref "Q4") (pin "1") (pinfunction "S_1") (pintype "passive"))
      (node (ref "R36") (pin "2") (pinfunction "2_2") (pintype "passive"))
    )
    (net (code "38") (name "Net-(Q4-D)") (class "Default")
      (node (ref "C9") (pin "+") (pinfunction "+_+") (pintype "passive"))
      (node (ref "Q4") (pin "3") (pinfunction "D_3") (pintype "passive"))
      (node (ref "R11") (pin "2") (pinfunction "2_2") (pintype "passive"))
    )
    (net (code "39") (name "Net-(Q4-G)") (class "Default")
      (node (ref "D4") (pin "A") (pinfunction "A_A") (pintype "passive"))
      (node (ref "Q4") (pin "2") (pinfunction "G_2") (pintype "passive"))
    )
    (net (code "40") (name "Net-(Q5-B)") (class "Default")
      (node (ref "C13") (pin "-") (pinfunction "-_-") (pintype "passive"))
      (node (ref "Q5") (pin "1") (pinfunction "B_1") (pintype "passive"))
      (node (ref "R21") (pin "2") (pinfunction "2_2") (pintype "passive"))
    )
    (net (code "41") (name "Net-(Q5-E)") (class "Default")
      (node (ref "C10") (pin "-") (pinfunction "-_-") (pintype "passive"))
      (node (ref "Q5") (pin "3") (pinfunction "E_3") (pintype "passive"))
      (node (ref "R12") (pin "2") (pinfunction "2_2") (pintype "passive"))
    )
    (net (code "42") (name "Net-(Q6-G)") (class "Default")
      (node (ref "C12") (pin "1") (pinfunction "1_1") (pintype "passive"))
      (node (ref "Q6") (pin "2") (pinfunction "G_2") (pintype "passive"))
      (node (ref "R16") (pin "2") (pinfunction "2_2") (pintype "passive"))
    )
    (net (code "43") (name "Net-(Q6-S)") (class "Default")
      (node (ref "C13") (pin "+") (pinfunction "+_+") (pintype "passive"))
      (node (ref "C15") (pin "+") (pinfunction "+_+") (pintype "passive"))
      (node (ref "Q6") (pin "1") (pinfunction "S_1") (pintype "passive"))
      (node (ref "R17") (pin "2") (pinfunction "2_2") (pintype "passive"))
    )
    (net (code "44") (name "Net-(Q7-B)") (class "Default")
      (node (ref "C14") (pin "+") (pinfunction "+_+") (pintype "passive"))
      (node (ref "Q7") (pin "1") (pinfunction "B_1") (pintype "passive"))
      (node (ref "R15") (pin "1") (pinfunction "1_1") (pintype "passive"))
    )
    (net (code "45") (name "Net-(Q8-B)") (class "Default")
      (node (ref "Q8") (pin "2") (pinfunction "B_2") (pintype "passive"))
      (node (ref "R25") (pin "1") (pinfunction "1_1") (pintype "passive"))
      (node (ref "R26") (pin "1") (pinfunction "1_1") (pintype "passive"))
    )
    (net (code "46") (name "Net-(Q8-C)") (class "Default")
      (node (ref "Q8") (pin "1") (pinfunction "C_1") (pintype "passive"))
      (node (ref "R23") (pin "2") (pinfunction "2_2") (pintype "passive"))
      (node (ref "R24") (pin "2") (pinfunction "2_2") (pintype "passive"))
    )
    (net (code "47") (name "Net-(Q9-B)") (class "Default")
      (node (ref "Q9") (pin "2") (pinfunction "B_2") (pintype "passive"))
      (node (ref "R29") (pin "1") (pinfunction "1_1") (pintype "passive"))
    )
    (net (code "48") (name "Net-(Q9-C)") (class "Default")
      (node (ref "Q9") (pin "1") (pinfunction "C_1") (pintype "passive"))
      (node (ref "R26") (pin "2") (pinfunction "2_2") (pintype "passive"))
      (node (ref "R30") (pin "2") (pinfunction "2_2") (pintype "passive"))
      (node (ref "R31") (pin "1") (pinfunction "1_1") (pintype "passive"))
    )
    (net (code "49") (name "Net-(Q10-D)") (class "Default")
      (node (ref "Q10") (pin "3") (pinfunction "D_3") (pintype "passive"))
      (node (ref "R32") (pin "2") (pinfunction "2_2") (pintype "passive"))
      (node (ref "R33") (pin "1") (pinfunction "1_1") (pintype "passive"))
      (node (ref "R44") (pin "2") (pinfunction "2_2") (pintype "passive"))
    )
    (net (code "50") (name "Net-(Q10-G)") (class "Default")
      (node (ref "D5") (pin "A") (pinfunction "A_A") (pintype "passive"))
      (node (ref "Q10") (pin "2") (pinfunction "G_2") (pintype "passive"))
    )
    (net (code "51") (name "Net-(Q10-S)") (class "Default")
      (node (ref "C21") (pin "1") (pinfunction "1_1") (pintype "passive"))
      (node (ref "Q10") (pin "1") (pinfunction "S_1") (pintype "passive"))
      (node (ref "R32") (pin "1") (pinfunction "1_1") (pintype "passive"))
    )
    (net (code "52") (name "Net-(Q11-B)") (class "Default")
      (node (ref "C23") (pin "-") (pinfunction "-_-") (pintype "passive"))
      (node (ref "Q11") (pin "1") (pinfunction "B_1") (pintype "passive"))
      (node (ref "R37") (pin "2") (pinfunction "2_2") (pintype "passive"))
    )
    (net (code "53") (name "Net-(Q11-E)") (class "Default")
      (node (ref "C24") (pin "+") (pinfunction "+_+") (pintype "passive"))
      (node (ref "Q11") (pin "3") (pinfunction "E_3") (pintype "passive"))
      (node (ref "R38") (pin "2") (pinfunction "2_2") (pintype "passive"))
    )
    (net (code "54") (name "Net-(Q12-B)") (class "Default")
      (node (ref "C28") (pin "2") (pinfunction "2_2") (pintype "passive"))
      (node (ref "Q12") (pin "1") (pinfunction "B_1") (pintype "passive"))
      (node (ref "R44") (pin "1") (pinfunction "1_1") (pintype "passive"))
    )
    (net (code "55") (name "Net-(Q12-E)") (class "Default")
      (node (ref "Q12") (pin "3") (pinfunction "E_3") (pintype "passive"))
      (node (ref "R42") (pin "2") (pinfunction "2_2") (pintype "passive"))
      (node (ref "R43") (pin "2") (pinfunction "2_2") (pintype "passive"))
    )
    (net (code "56") (name "Net-(Q13-B)") (class "Default")
      (node (ref "C29") (pin "2") (pinfunction "2_2") (pintype "passive"))
      (node (ref "C30") (pin "-") (pinfunction "-_-") (pintype "passive"))
      (node (ref "Q13") (pin "1") (pinfunction "B_1") (pintype "passive"))
      (node (ref "R35") (pin "2") (pinfunction "2_2") (pintype "passive"))
      (node (ref "R48") (pin "1") (pinfunction "1_1") (pintype "passive"))
    )
    (net (code "57") (name "Net-(Q13-C)") (class "Default")
      (node (ref "C28") (pin "1") (pinfunction "1_1") (pintype "passive"))
      (node (ref "C29") (pin "1") (pinfunction "1_1") (pintype "passive"))
      (node (ref "Q13") (pin "2") (pinfunction "C_2") (pintype "passive"))
      (node (ref "R33") (pin "2") (pinfunction "2_2") (pintype "passive"))
      (node (ref "R45") (pin "1") (pinfunction "1_1") (pintype "passive"))
      (node (ref "R46") (pin "1") (pinfunction "1_1") (pintype "passive"))
      (node (ref "R47") (pin "1") (pinfunction "1_1") (pintype "passive"))
    )
    (net (code "58") (name "Net-(Q13-E)") (class "Default")
      (node (ref "C22") (pin "+") (pinfunction "+_+") (pintype "passive"))
      (node (ref "Q13") (pin "3") (pinfunction "E_3") (pintype "passive"))
      (node (ref "R34") (pin "2") (pinfunction "2_2") (pintype "passive"))
    )
    (net (code "59") (name "Net-(Q14-D)") (class "Default")
      (node (ref "C39") (pin "1") (pinfunction "1_1") (pintype "passive"))
      (node (ref "Q14") (pin "3") (pinfunction "D_3") (pintype "passive"))
      (node (ref "R61") (pin "2") (pinfunction "2_2") (pintype "passive"))
    )
    (net (code "60") (name "Net-(Q14-G)") (class "Default")
      (node (ref "D7") (pin "A") (pinfunction "A_A") (pintype "passive"))
      (node (ref "Q14") (pin "2") (pinfunction "G_2") (pintype "passive"))
    )
    (net (code "61") (name "Net-(Q14-S)") (class "Default")
      (node (ref "Q14") (pin "1") (pinfunction "S_1") (pintype "passive"))
      (node (ref "Q15") (pin "1") (pinfunction "S_1") (pintype "passive"))
      (node (ref "Q16") (pin "2") (pinfunction "G_2") (pintype "passive"))
      (node (ref "R49") (pin "2") (pinfunction "2_2") (pintype "passive"))
    )
    (net (code "62") (name "Net-(Q15-D)") (class "Default")
      (node (ref "Q15") (pin "3") (pinfunction "D_3") (pintype "passive"))
      (node (ref "R64") (pin "2") (pinfunction "2_2") (pintype "passive"))
      (node (ref "R68") (pin "2") (pinfunction "2_2") (pintype "passive"))
    )
    (net (code "63") (name "Net-(Q15-G)") (class "Default")
      (node (ref "D6") (pin "A") (pinfunction "A_A") (pintype "passive"))
      (node (ref "Q15") (pin "2") (pinfunction "G_2") (pintype "passive"))
    )
    (net (code "64") (name "Net-(Q16-D)") (class "Default")
      (node (ref "C31") (pin "2") (pinfunction "2_2") (pintype "passive"))
      (node (ref "Q16") (pin "3") (pinfunction "D_3") (pintype "passive"))
      (node (ref "Q17") (pin "2") (pinfunction "B_2") (pintype "passive"))
      (node (ref "R50") (pin "1") (pinfunction "1_1") (pintype "passive"))
    )
    (net (code "65") (name "Net-(Q16-S)") (class "Default")
      (node (ref "Q16") (pin "1") (pinfunction "S_1") (pintype "passive"))
      (node (ref "Q19") (pin "1") (pinfunction "S_1") (pintype "passive"))
      (node (ref "R53") (pin "2") (pinfunction "2_2") (pintype "passive"))
    )
    (net (code "66") (name "Net-(Q17-C)") (class "Default")
      (node (ref "C31") (pin "1") (pinfunction "1_1") (pintype "passive"))
      (node (ref "Q17") (pin "1") (pinfunction "C_1") (pintype "passive"))
      (node (ref "Q18") (pin "1") (pinfunction "B_1") (pintype "passive"))
      (node (ref "R51") (pin "2") (pinfunction "2_2") (pintype "passive"))
    )
    (net (code "67") (name "Net-(Q18-E)") (class "Default")
      (node (ref "C32") (pin "1") (pinfunction "1_1") (pintype "passive"))
      (node (ref "C35") (pin "+") (pinfunction "+_+") (pintype "passive"))
      (node (ref "Q18") (pin "3") (pinfunction "E_3") (pintype "passive"))
      (node (ref "Q20") (pin "1") (pinfunction "S_1") (pintype "passive"))
      (node (ref "R52") (pin "2") (pinfunction "2_2") (pintype "passive"))
      (node (ref "R56") (pin "2") (pinfunction "2_2") (pintype "passive"))
      (node (ref "VR1") (pin "2") (pinfunction "2_2") (pintype "passive"))
      (node (ref "VR1") (pin "3") (pinfunction "3_3") (pintype "passive"))
    )
    (net (code "68") (name "Net-(Q19-G)") (class "Default")
      (node (ref "C32") (pin "2") (pinfunction "2_2") (pintype "passive"))
      (node (ref "D8") (pin "C") (pinfunction "C_C") (pintype "passive"))
      (node (ref "D9") (pin "A") (pinfunction "A_A") (pintype "passive"))
      (node (ref "Q19") (pin "2") (pinfunction "G_2") (pintype "passive"))
      (node (ref "R54") (pin "2") (pinfunction "2_2") (pintype "passive"))
      (node (ref "R55") (pin "2") (pinfunction "2_2") (pintype "passive"))
    )
    (net (code "69") (name "Net-(Q20-D)") (class "Default")
      (node (ref "C34") (pin "1") (pinfunction "1_1") (pintype "passive"))
      (node (ref "Q20") (pin "3") (pinfunction "D_3") (pintype "passive"))
      (node (ref "R56") (pin "1") (pinfunction "1_1") (pintype "passive"))
    )
    (net (code "70") (name "Net-(Q20-G)") (class "Default")
      (node (ref "D10") (pin "A") (pinfunction "A_A") (pintype "passive"))
      (node (ref "Q20") (pin "2") (pinfunction "G_2") (pintype "passive"))
    )
    (net (code "71") (name "Net-(Q21-D)") (class "Default")
      (node (ref "C15") (pin "-") (pinfunction "-_-") (pintype "passive"))
      (node (ref "Q21") (pin "3") (pinfunction "D_3") (pintype "passive"))
      (node (ref "R18") (pin "2") (pinfunction "2_2") (pintype "passive"))
    )
    (net (code "72") (name "Net-(Q21-G)") (class "Default")
      (node (ref "D13") (pin "A") (pinfunction "A_A") (pintype "passive"))
      (node (ref "Q21") (pin "2") (pinfunction "G_2") (pintype "passive"))
    )
    (net (code "73") (name "Net-(Q21-S)") (class "Default")
      (node (ref "C38") (pin "+") (pinfunction "+_+") (pintype "passive"))
      (node (ref "Q21") (pin "1") (pinfunction "S_1") (pintype "passive"))
      (node (ref "R60") (pin "2") (pinfunction "2_2") (pintype "passive"))
    )
    (net (code "74") (name "Net-(Q22-B)") (class "Default")
      (node (ref "C40") (pin "1") (pinfunction "1_1") (pintype "passive"))
      (node (ref "Q22") (pin "1") (pinfunction "B_1") (pintype "passive"))
      (node (ref "R63") (pin "2") (pinfunction "2_2") (pintype "passive"))
    )
    (net (code "75") (name "Net-(Q22-C)") (class "Default")
      (node (ref "C39") (pin "2") (pinfunction "2_2") (pintype "passive"))
      (node (ref "C41") (pin "2") (pinfunction "2_2") (pintype "passive"))
      (node (ref "Q22") (pin "2") (pinfunction "C_2") (pintype "passive"))
      (node (ref "R65") (pin "1") (pinfunction "1_1") (pintype "passive"))
      (node (ref "R69") (pin "1") (pinfunction "1_1") (pintype "passive"))
    )
    (net (code "76") (name "Net-(Q22-E)") (class "Default")
      (node (ref "Q22") (pin "3") (pinfunction "E_3") (pintype "passive"))
      (node (ref "R66") (pin "2") (pinfunction "2_2") (pintype "passive"))
      (node (ref "R67") (pin "2") (pinfunction "2_2") (pintype "passive"))
    )
    (net (code "77") (name "Net-(Q23-B)") (class "Default")
      (node (ref "C44") (pin "1") (pinfunction "1_1") (pintype "passive"))
      (node (ref "Q23") (pin "1") (pinfunction "B_1") (pintype "passive"))
      (node (ref "R70") (pin "2") (pinfunction "2_2") (pintype "passive"))
    )
    (net (code "78") (name "Net-(Q23-E)") (class "Default")
      (node (ref "C43") (pin "2") (pinfunction "2_2") (pintype "passive"))
      (node (ref "C45") (pin "2") (pinfunction "2_2") (pintype "passive"))
      (node (ref "Q23") (pin "3") (pinfunction "E_3") (pintype "passive"))
      (node (ref "R72") (pin "2") (pinfunction "2_2") (pintype "passive"))
    )
    (net (code "79") (name "Net-(R45-Pad2)") (class "Default")
      (node (ref "R45") (pin "2") (pinfunction "2_2") (pintype "passive"))
      (node (ref "VR2") (pin "1") (pinfunction "1_1") (pintype "passive"))
    )
    (net (code "80") (name "Net-(R55-Pad1)") (class "Default")
      (node (ref "R55") (pin "1") (pinfunction "1_1") (pintype "passive"))
      (node (ref "VR1") (pin "1") (pinfunction "1_1") (pintype "passive"))
    )
    (net (code "81") (name "Net-(R59-Pad2)") (class "Default")
      (node (ref "R59") (pin "2") (pinfunction "2_2") (pintype "passive"))
      (node (ref "VR2") (pin "3") (pinfunction "3_3") (pintype "passive"))
    )
    (net (code "82") (name "Net-(SW1-P)") (class "Default")
      (node (ref "R2") (pin "2") (pinfunction "2_2") (pintype "passive"))
      (node (ref "SW1") (pin "1") (pinfunction "P_1") (pintype "passive"))
    )
    (net (code "83") (name "Net-(SW2-P)") (class "Default")
      (node (ref "R1 ") (pin "2") (pinfunction "2_2") (pintype "passive"))
      (node (ref "SW2") (pin "2") (pinfunction "P_2") (pintype "passive"))
    )
    (net (code "84") (name "OUT") (class "Default")
      (node (ref "R40") (pin "2") (pinfunction "2_2") (pintype "passive"))
    )
    (net (code "85") (name "VA") (class "Default")
      (node (ref "C16") (pin "+") (pinfunction "+_+") (pintype "passive"))
      (node (ref "Q11") (pin "2") (pinfunction "C_2") (pintype "passive"))
      (node (ref "Q12") (pin "2") (pinfunction "C_2") (pintype "passive"))
      (node (ref "Q17") (pin "3") (pinfunction "E_3") (pintype "passive"))
      (node (ref "Q18") (pin "2") (pinfunction "C_2") (pintype "passive"))
      (node (ref "Q19") (pin "3") (pinfunction "D_3") (pintype "passive"))
      (node (ref "Q23") (pin "2") (pinfunction "C_2") (pintype "passive"))
      (node (ref "Q5") (pin "2") (pinfunction "C_2") (pintype "passive"))
      (node (ref "Q6") (pin "3") (pinfunction "D_3") (pintype "passive"))
      (node (ref "Q7") (pin "3") (pinfunction "E_3") (pintype "passive"))
      (node (ref "R20") (pin "2") (pinfunction "2_2") (pintype "passive"))
      (node (ref "R47") (pin "2") (pinfunction "2_2") (pintype "passive"))
      (node (ref "R48") (pin "2") (pinfunction "2_2") (pintype "passive"))
      (node (ref "R50") (pin "2") (pinfunction "2_2") (pintype "passive"))
      (node (ref "R65") (pin "2") (pinfunction "2_2") (pintype "passive"))
    )
    (net (code "86") (name "VB") (class "Default")
      (node (ref "C17") (pin "+") (pinfunction "+_+") (pintype "passive"))
      (node (ref "R11") (pin "1") (pinfunction "1_1") (pintype "passive"))
      (node (ref "R14") (pin "1") (pinfunction "1_1") (pintype "passive"))
      (node (ref "R16") (pin "1") (pinfunction "1_1") (pintype "passive"))
      (node (ref "R18") (pin "1") (pinfunction "1_1") (pintype "passive"))
      (node (ref "R19") (pin "2") (pinfunction "2_2") (pintype "passive"))
      (node (ref "R20") (pin "1") (pinfunction "1_1") (pintype "passive"))
      (node (ref "R21") (pin "1") (pinfunction "1_1") (pintype "passive"))
      (node (ref "R36") (pin "1") (pinfunction "1_1") (pintype "passive"))
      (node (ref "R37") (pin "1") (pinfunction "1_1") (pintype "passive"))
      (node (ref "R49") (pin "1") (pinfunction "1_1") (pintype "passive"))
      (node (ref "R60") (pin "1") (pinfunction "1_1") (pintype "passive"))
      (node (ref "R61") (pin "1") (pinfunction "1_1") (pintype "passive"))
      (node (ref "R63") (pin "1") (pinfunction "1_1") (pintype "passive"))
      (node (ref "R71") (pin "1") (pinfunction "1_1") (pintype "passive"))
    )
    (net (code "87") (name "unconnected-(SW2-S-Pad3)") (class "Default")
      (node (ref "SW2") (pin "3") (pinfunction "S_3") (pintype "passive"))
    )
  )
)
